# SH4_-_3_3V_LINEAR_REGULATOR.net
KiCad netlist of a schematic drawn in Altium Designer
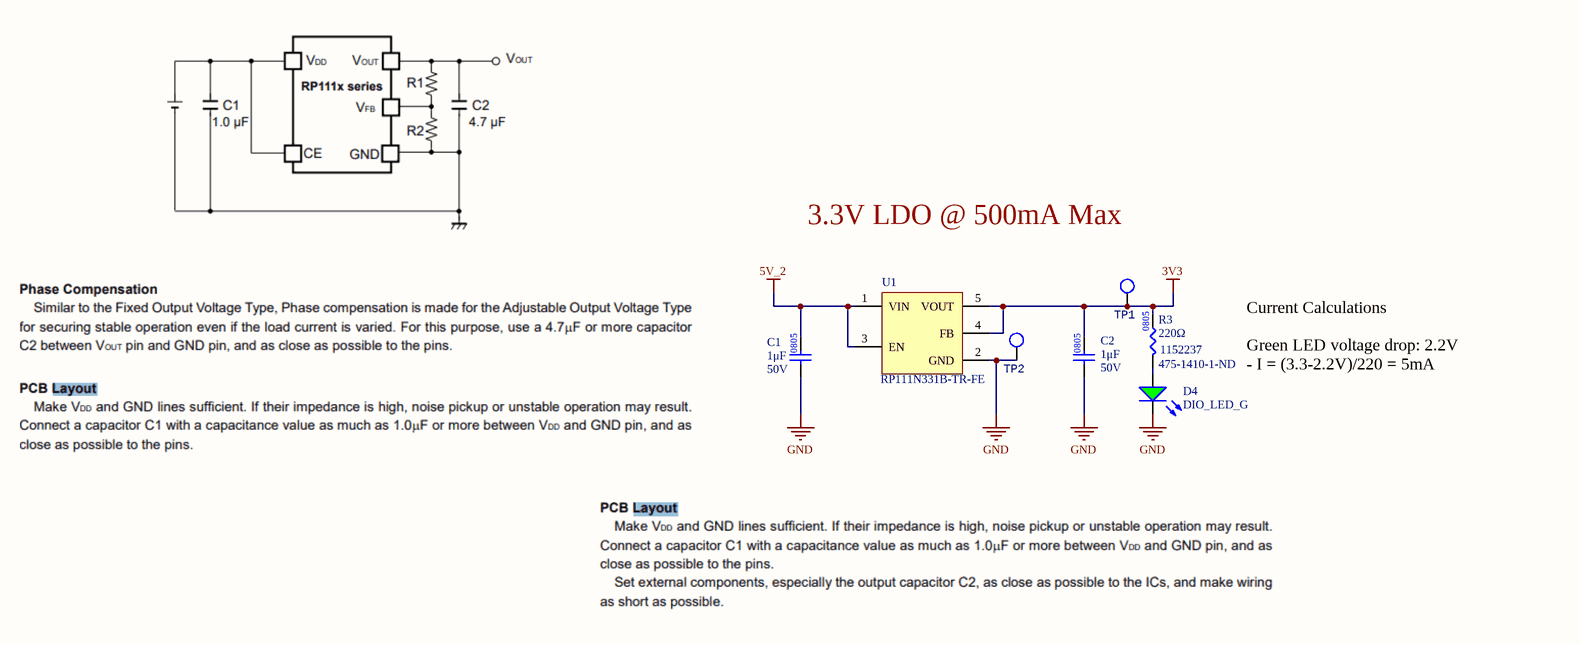
[diagram p0: SH4 - 3.3V LINEAR REGULATOR.SchDoc]

(export (version "E")
  (design (tool "Eeschema 10.0.6"))
  (components
    (comp (ref "C1")
      (value "1μF")
      (footprint "CAP2012")
      (description "CAP CER 1UF 50V X7R 0805")
      (fields
        (field (name "VOLTAGE RATING") "50V")
        (field (name "LCSC PART #") "C28323")
        (field (name "Comment") "CAP_1uF_50V_0805")
      )
      (libsource (lib "UWRT_Schematic_Library_2020") (part "CAP_1uF_50V_0805"))
    )
    (comp (ref "C2")
      (value "1μF")
      (footprint "CAP2012")
      (description "CAP CER 1UF 50V X7R 0805")
      (fields
        (field (name "VOLTAGE RATING") "50V")
        (field (name "LCSC PART #") "C28323")
        (field (name "Comment") "CAP_1uF_50V_0805")
      )
      (libsource (lib "UWRT_Schematic_Library_2020") (part "CAP_1uF_50V_0805"))
    )
    (comp (ref "D4")
      (value "DIO_LED_G")
      (footprint "LED_0805_GREEN")
      (description "LED GREEN DIFFUSED 0805 SMD")
      (fields
        (field (name "SUPPLIER PART NUMBER 1") "475-1410-1-ND")
        (field (name "SUPPLIER PART NUMBER 2") "1152237")
      )
      (libsource (lib "UWRT_Schematic_Library_2020") (part "DIO_LED_G"))
    )
    (comp (ref "R3")
      (value "220Ω")
      (footprint "RES0805")
      (description "RES 220 OHM 5% 1/2W 0805")
      (fields (field (name "LCSC PART #") "C17557") (field (name "Comment") "RES_220Ω_0805_5%"))
      (libsource (lib "UWRT_Schematic_Library_2020") (part "RES_220Ω_0805_5%"))
    )
    (comp (ref "TP1")
      (value "TESTPOINT_LOOP")
      (footprint "TESTPOINT_LOOP")
      (description "TESTPOINT THRUHOLE")
      (libsource (lib "UWRT_Schematic_Library_2020") (part "TESTPOINT_LOOP"))
    )
    (comp (ref "TP2")
      (value "TESTPOINT_LOOP")
      (footprint "TESTPOINT_LOOP")
      (description "TESTPOINT THRUHOLE")
      (libsource (lib "UWRT_Schematic_Library_2020") (part "TESTPOINT_LOOP"))
    )
    (comp (ref "U1")
      (value "LDO_3.3V_500mA")
      (footprint "SOT23-5")
      (description "IC REG LINEAR 3.3V 500MA SOT23-5")
      (fields (field (name "MANUFACTURER PART NUMBER 1") "RP111N331B-TR-FE"))
      (libsource (lib "UWRT_Schematic_Library_2020") (part "LDO_3.3V_500mA"))
    )
  )
  (nets
    (net (code "1") (name "3V3") (class "Default")
      (node (ref "C2") (pin "2") (pinfunction "2_2") (pintype "passive"))
      (node (ref "R3") (pin "2") (pinfunction "2_2") (pintype "passive"))
      (node (ref "TP1") (pin "1") (pintype "passive"))
      (node (ref "U1") (pin "4") (pinfunction "FB_4") (pintype "passive"))
      (node (ref "U1") (pin "5") (pinfunction "VOUT_5") (pintype "passive"))
    )
    (net (code "2") (name "5V_2") (class "Default")
      (node (ref "C1") (pin "2") (pinfunction "2_2") (pintype "passive"))
      (node (ref "U1") (pin "1") (pinfunction "VIN_1") (pintype "passive"))
      (node (ref "U1") (pin "3") (pinfunction "EN_3") (pintype "passive"))
    )
    (net (code "3") (name "GND") (class "Default")
      (node (ref "C1") (pin "1") (pinfunction "1_1") (pintype "passive"))
      (node (ref "C2") (pin "1") (pinfunction "1_1") (pintype "passive"))
      (node (ref "D4") (pin "2") (pinfunction "K_2") (pintype "passive"))
      (node (ref "TP2") (pin "1") (pintype "passive"))
      (node (ref "U1") (pin "2") (pinfunction "GND_2") (pintype "passive"))
    )
    (net (code "4") (name "Net-(D4-A)") (class "Default")
      (node (ref "D4") (pin "1") (pinfunction "A_1") (pintype "passive"))
      (node (ref "R3") (pin "1") (pinfunction "1_1") (pintype "passive"))
    )
  )
)
